# dc10_revA.net
KiCad netlist of a schematic drawn in EAGLE
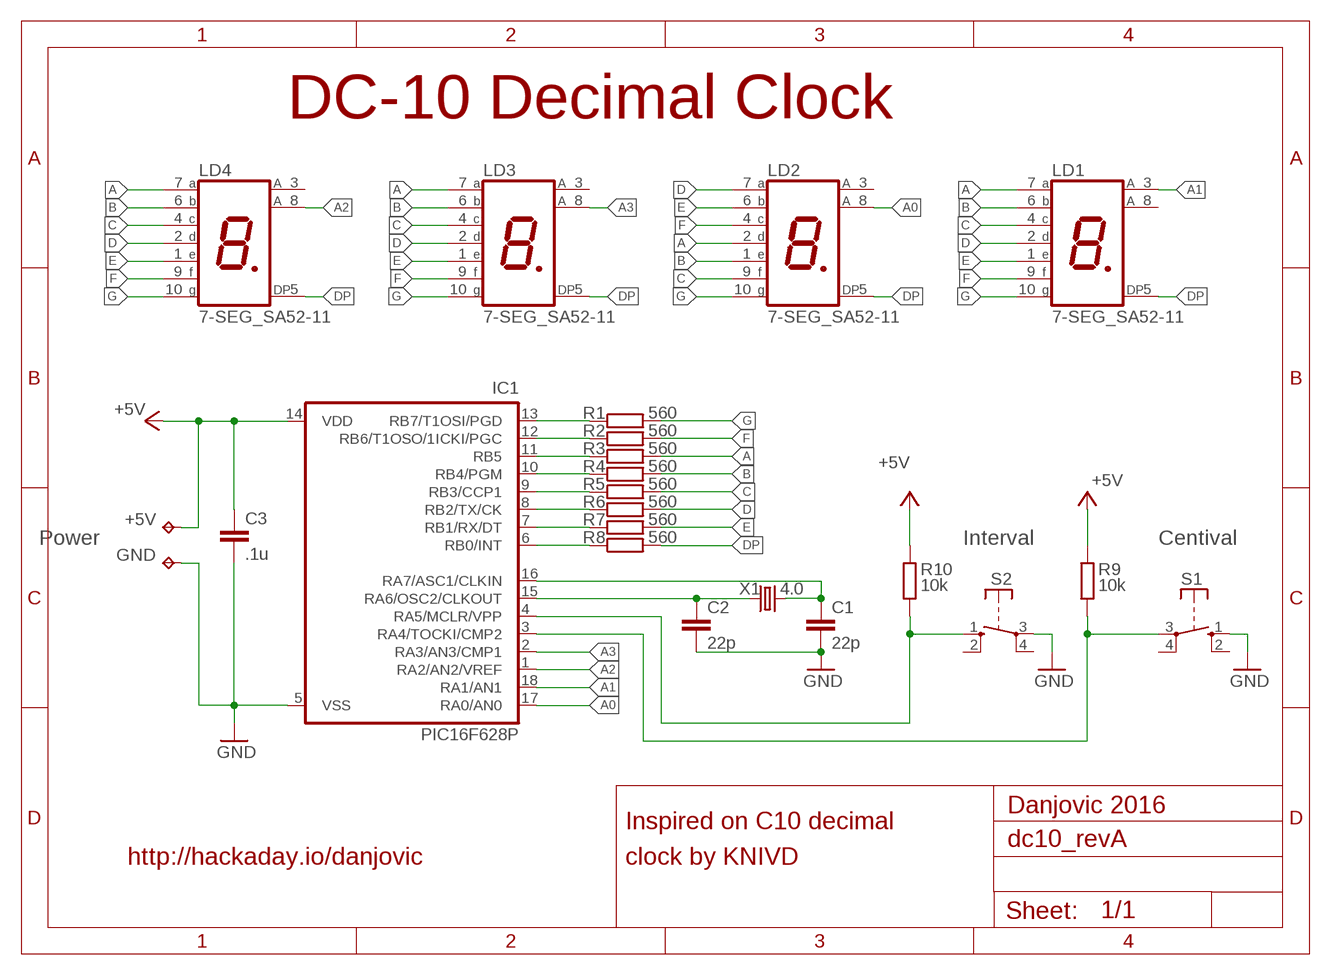
[diagram p0: schematic, sheet 1]

(export (version "E")
  (design (tool "Eeschema 10.0.6"))
  (components
    (comp (ref "+5V")
      (value "TPPAD1-13")
      (footprint "eagle-import:P1-13")
      (libsource (lib "eagle-import") (part "TPPAD1-13"))
    )
    (comp (ref "C1")
      (value "22p")
      (footprint "eagle-import:C050-024X044")
      (libsource (lib "eagle-import") (part "C-EU050-024X044"))
    )
    (comp (ref "C2")
      (value "22p")
      (footprint "eagle-import:C050-024X044")
      (libsource (lib "eagle-import") (part "C-EU050-024X044"))
    )
    (comp (ref "C3")
      (value ".1u")
      (footprint "eagle-import:C050-024X044")
      (libsource (lib "eagle-import") (part "C-EU050-024X044"))
    )
    (comp (ref "GND")
      (value "TPPAD1-13")
      (footprint "eagle-import:P1-13")
      (libsource (lib "eagle-import") (part "TPPAD1-13"))
    )
    (comp (ref "IC1")
      (value "PIC16F628P")
      (footprint "eagle-import:DIL18")
      (libsource (lib "eagle-import") (part "PIC16F628P"))
    )
    (comp (ref "LD1")
      (value "7-SEG_SA52-11")
      (footprint "eagle-import:SA52-11")
      (libsource (lib "eagle-import") (part "7-SEG_SA52-11"))
    )
    (comp (ref "LD2")
      (value "7-SEG_SA52-11")
      (footprint "eagle-import:SA52-11")
      (libsource (lib "eagle-import") (part "7-SEG_SA52-11"))
    )
    (comp (ref "LD3")
      (value "7-SEG_SA52-11")
      (footprint "eagle-import:SA52-11")
      (libsource (lib "eagle-import") (part "7-SEG_SA52-11"))
    )
    (comp (ref "LD4")
      (value "7-SEG_SA52-11")
      (footprint "eagle-import:SA52-11")
      (libsource (lib "eagle-import") (part "7-SEG_SA52-11"))
    )
    (comp (ref "R1")
      (value "560")
      (footprint "eagle-import:0204_7")
      (libsource (lib "eagle-import") (part "R-EU_0204/7"))
    )
    (comp (ref "R2")
      (value "560")
      (footprint "eagle-import:0204_7")
      (libsource (lib "eagle-import") (part "R-EU_0204/7"))
    )
    (comp (ref "R3")
      (value "560")
      (footprint "eagle-import:0204_7")
      (libsource (lib "eagle-import") (part "R-EU_0204/7"))
    )
    (comp (ref "R4")
      (value "560")
      (footprint "eagle-import:0204_7")
      (libsource (lib "eagle-import") (part "R-EU_0204/7"))
    )
    (comp (ref "R5")
      (value "560")
      (footprint "eagle-import:0204_7")
      (libsource (lib "eagle-import") (part "R-EU_0204/7"))
    )
    (comp (ref "R6")
      (value "560")
      (footprint "eagle-import:0204_7")
      (libsource (lib "eagle-import") (part "R-EU_0204/7"))
    )
    (comp (ref "R7")
      (value "560")
      (footprint "eagle-import:0204_7")
      (libsource (lib "eagle-import") (part "R-EU_0204/7"))
    )
    (comp (ref "R8")
      (value "560")
      (footprint "eagle-import:0204_7")
      (libsource (lib "eagle-import") (part "R-EU_0204/7"))
    )
    (comp (ref "R9")
      (value "10k")
      (footprint "eagle-import:0204_7")
      (libsource (lib "eagle-import") (part "R-EU_0204/7"))
    )
    (comp (ref "R10")
      (value "10k")
      (footprint "eagle-import:0204_7")
      (libsource (lib "eagle-import") (part "R-EU_0204/7"))
    )
    (comp (ref "S1")
      (value "RACON12")
      (footprint "eagle-import:RACON12")
      (libsource (lib "eagle-import") (part "RACON12"))
    )
    (comp (ref "S2")
      (value "RACON12")
      (footprint "eagle-import:RACON12")
      (libsource (lib "eagle-import") (part "RACON12"))
    )
    (comp (ref "X1")
      (value "4.0")
      (footprint "eagle-import:HC49U-V")
      (libsource (lib "eagle-import") (part "CRYSTALHC49U-V"))
    )
  )
  (nets
    (net (code "1") (name "+5V") (class "Default")
      (node (ref "+5V") (pin "1") (pinfunction "TP_1") (pintype "input"))
      (node (ref "C3") (pin "1") (pinfunction "1_1") (pintype "passive"))
      (node (ref "IC1") (pin "14") (pinfunction "VDD_14") (pintype "power_in"))
      (node (ref "R10") (pin "1") (pinfunction "1_1") (pintype "passive"))
      (node (ref "R9") (pin "1") (pinfunction "1_1") (pintype "passive"))
    )
    (net (code "2") (name "A") (class "Default")
      (node (ref "LD1") (pin "7") (pinfunction "A_7") (pintype "passive"))
      (node (ref "LD2") (pin "2") (pinfunction "D_2") (pintype "passive"))
      (node (ref "LD3") (pin "7") (pinfunction "A_7") (pintype "passive"))
      (node (ref "LD4") (pin "7") (pinfunction "A_7") (pintype "passive"))
      (node (ref "R3") (pin "2") (pinfunction "2_2") (pintype "passive"))
    )
    (net (code "3") (name "A0") (class "Default")
      (node (ref "IC1") (pin "17") (pinfunction "RA0/AN0_17") (pintype "bidirectional"))
      (node (ref "LD2") (pin "8") (pinfunction "A_8") (pintype "passive"))
    )
    (net (code "4") (name "A1") (class "Default")
      (node (ref "IC1") (pin "18") (pinfunction "RA1/AN1_18") (pintype "bidirectional"))
      (node (ref "LD1") (pin "3") (pinfunction "A_3") (pintype "passive"))
    )
    (net (code "5") (name "A2") (class "Default")
      (node (ref "IC1") (pin "1") (pinfunction "RA2/AN2/VREF_1") (pintype "bidirectional"))
      (node (ref "LD4") (pin "8") (pinfunction "A_8") (pintype "passive"))
    )
    (net (code "6") (name "A3") (class "Default")
      (node (ref "IC1") (pin "2") (pinfunction "RA3/AN3/CMP1_2") (pintype "bidirectional"))
      (node (ref "LD3") (pin "8") (pinfunction "A_8") (pintype "passive"))
    )
    (net (code "7") (name "B") (class "Default")
      (node (ref "LD1") (pin "6") (pinfunction "B_6") (pintype "passive"))
      (node (ref "LD2") (pin "1") (pinfunction "E_1") (pintype "passive"))
      (node (ref "LD3") (pin "6") (pinfunction "B_6") (pintype "passive"))
      (node (ref "LD4") (pin "6") (pinfunction "B_6") (pintype "passive"))
      (node (ref "R4") (pin "2") (pinfunction "2_2") (pintype "passive"))
    )
    (net (code "8") (name "C") (class "Default")
      (node (ref "LD1") (pin "4") (pinfunction "C_4") (pintype "passive"))
      (node (ref "LD2") (pin "9") (pinfunction "F_9") (pintype "passive"))
      (node (ref "LD3") (pin "4") (pinfunction "C_4") (pintype "passive"))
      (node (ref "LD4") (pin "4") (pinfunction "C_4") (pintype "passive"))
      (node (ref "R5") (pin "2") (pinfunction "2_2") (pintype "passive"))
    )
    (net (code "9") (name "D") (class "Default")
      (node (ref "LD1") (pin "2") (pinfunction "D_2") (pintype "passive"))
      (node (ref "LD2") (pin "7") (pinfunction "A_7") (pintype "passive"))
      (node (ref "LD3") (pin "2") (pinfunction "D_2") (pintype "passive"))
      (node (ref "LD4") (pin "2") (pinfunction "D_2") (pintype "passive"))
      (node (ref "R6") (pin "2") (pinfunction "2_2") (pintype "passive"))
    )
    (net (code "10") (name "DP") (class "Default")
      (node (ref "LD1") (pin "5") (pinfunction "DP_5") (pintype "passive"))
      (node (ref "LD2") (pin "5") (pinfunction "DP_5") (pintype "passive"))
      (node (ref "LD3") (pin "5") (pinfunction "DP_5") (pintype "passive"))
      (node (ref "LD4") (pin "5") (pinfunction "DP_5") (pintype "passive"))
      (node (ref "R8") (pin "2") (pinfunction "2_2") (pintype "passive"))
    )
    (net (code "11") (name "E") (class "Default")
      (node (ref "LD1") (pin "1") (pinfunction "E_1") (pintype "passive"))
      (node (ref "LD2") (pin "6") (pinfunction "B_6") (pintype "passive"))
      (node (ref "LD3") (pin "1") (pinfunction "E_1") (pintype "passive"))
      (node (ref "LD4") (pin "1") (pinfunction "E_1") (pintype "passive"))
      (node (ref "R7") (pin "2") (pinfunction "2_2") (pintype "passive"))
    )
    (net (code "12") (name "F") (class "Default")
      (node (ref "LD1") (pin "9") (pinfunction "F_9") (pintype "passive"))
      (node (ref "LD2") (pin "4") (pinfunction "C_4") (pintype "passive"))
      (node (ref "LD3") (pin "9") (pinfunction "F_9") (pintype "passive"))
      (node (ref "LD4") (pin "9") (pinfunction "F_9") (pintype "passive"))
      (node (ref "R2") (pin "2") (pinfunction "2_2") (pintype "passive"))
    )
    (net (code "13") (name "G") (class "Default")
      (node (ref "LD1") (pin "10") (pinfunction "G_10") (pintype "passive"))
      (node (ref "LD2") (pin "10") (pinfunction "G_10") (pintype "passive"))
      (node (ref "LD3") (pin "10") (pinfunction "G_10") (pintype "passive"))
      (node (ref "LD4") (pin "10") (pinfunction "G_10") (pintype "passive"))
      (node (ref "R1") (pin "2") (pinfunction "2_2") (pintype "passive"))
    )
    (net (code "14") (name "GND") (class "Default")
      (node (ref "C1") (pin "2") (pinfunction "2_2") (pintype "passive"))
      (node (ref "C2") (pin "2") (pinfunction "2_2") (pintype "passive"))
      (node (ref "C3") (pin "2") (pinfunction "2_2") (pintype "passive"))
      (node (ref "GND") (pin "1") (pinfunction "TP_1") (pintype "input"))
      (node (ref "IC1") (pin "5") (pinfunction "VSS_5") (pintype "power_in"))
      (node (ref "S1") (pin "1") (pinfunction "S_1") (pintype "passive"))
      (node (ref "S2") (pin "3") (pinfunction "P_3") (pintype "passive"))
    )
    (net (code "15") (name "Net-(IC1-RA4{slash}TOCKI{slash}CMP2)") (class "Default")
      (node (ref "IC1") (pin "3") (pinfunction "RA4/TOCKI/CMP2_3") (pintype "bidirectional"))
      (node (ref "R9") (pin "2") (pinfunction "2_2") (pintype "passive"))
      (node (ref "S1") (pin "3") (pinfunction "P_3") (pintype "passive"))
    )
    (net (code "16") (name "Net-(IC1-RA5{slash}MCLR{slash}VPP)") (class "Default")
      (node (ref "IC1") (pin "4") (pinfunction "RA5/MCLR/VPP_4") (pintype "input"))
      (node (ref "R10") (pin "2") (pinfunction "2_2") (pintype "passive"))
      (node (ref "S2") (pin "1") (pinfunction "S_1") (pintype "passive"))
    )
    (net (code "17") (name "Net-(IC1-RA6{slash}OSC2{slash}CLKOUT)") (class "Default")
      (node (ref "C2") (pin "1") (pinfunction "1_1") (pintype "passive"))
      (node (ref "IC1") (pin "15") (pinfunction "RA6/OSC2/CLKOUT_15") (pintype "bidirectional"))
      (node (ref "X1") (pin "1") (pinfunction "1_1") (pintype "passive"))
    )
    (net (code "18") (name "Net-(IC1-RA7{slash}ASC1{slash}CLKIN)") (class "Default")
      (node (ref "C1") (pin "1") (pinfunction "1_1") (pintype "passive"))
      (node (ref "IC1") (pin "16") (pinfunction "RA7/ASC1/CLKIN_16") (pintype "bidirectional"))
      (node (ref "X1") (pin "2") (pinfunction "2_2") (pintype "passive"))
    )
    (net (code "19") (name "Net-(IC1-RB0{slash}INT)") (class "Default")
      (node (ref "IC1") (pin "6") (pinfunction "RB0/INT_6") (pintype "bidirectional"))
      (node (ref "R8") (pin "1") (pinfunction "1_1") (pintype "passive"))
    )
    (net (code "20") (name "Net-(IC1-RB1{slash}RX{slash}DT)") (class "Default")
      (node (ref "IC1") (pin "7") (pinfunction "RB1/RX/DT_7") (pintype "bidirectional"))
      (node (ref "R7") (pin "1") (pinfunction "1_1") (pintype "passive"))
    )
    (net (code "21") (name "Net-(IC1-RB2{slash}TX{slash}CK)") (class "Default")
      (node (ref "IC1") (pin "8") (pinfunction "RB2/TX/CK_8") (pintype "bidirectional"))
      (node (ref "R6") (pin "1") (pinfunction "1_1") (pintype "passive"))
    )
    (net (code "22") (name "Net-(IC1-RB3{slash}CCP1)") (class "Default")
      (node (ref "IC1") (pin "9") (pinfunction "RB3/CCP1_9") (pintype "bidirectional"))
      (node (ref "R5") (pin "1") (pinfunction "1_1") (pintype "passive"))
    )
    (net (code "23") (name "Net-(IC1-RB4{slash}PGM)") (class "Default")
      (node (ref "IC1") (pin "10") (pinfunction "RB4/PGM_10") (pintype "bidirectional"))
      (node (ref "R4") (pin "1") (pinfunction "1_1") (pintype "passive"))
    )
    (net (code "24") (name "Net-(IC1-RB5)") (class "Default")
      (node (ref "IC1") (pin "11") (pinfunction "RB5_11") (pintype "bidirectional"))
      (node (ref "R3") (pin "1") (pinfunction "1_1") (pintype "passive"))
    )
    (net (code "25") (name "Net-(IC1-RB6{slash}T1OSO{slash}1ICKI{slash}PGC)") (class "Default")
      (node (ref "IC1") (pin "12") (pinfunction "RB6/T1OSO/1ICKI/PGC_12") (pintype "bidirectional"))
      (node (ref "R2") (pin "1") (pinfunction "1_1") (pintype "passive"))
    )
    (net (code "26") (name "Net-(IC1-RB7{slash}T1OSI{slash}PGD)") (class "Default")
      (node (ref "IC1") (pin "13") (pinfunction "RB7/T1OSI/PGD_13") (pintype "bidirectional"))
      (node (ref "R1") (pin "1") (pinfunction "1_1") (pintype "passive"))
    )
    (net (code "27") (name "unconnected-(LD1-A-Pad8)") (class "Default")
      (node (ref "LD1") (pin "8") (pinfunction "A_8") (pintype "passive"))
    )
    (net (code "28") (name "unconnected-(LD2-A-Pad3)") (class "Default")
      (node (ref "LD2") (pin "3") (pinfunction "A_3") (pintype "passive"))
    )
    (net (code "29") (name "unconnected-(LD3-A-Pad3)") (class "Default")
      (node (ref "LD3") (pin "3") (pinfunction "A_3") (pintype "passive"))
    )
    (net (code "30") (name "unconnected-(LD4-A-Pad3)") (class "Default")
      (node (ref "LD4") (pin "3") (pinfunction "A_3") (pintype "passive"))
    )
    (net (code "31") (name "unconnected-(S1-P-Pad4)") (class "Default")
      (node (ref "S1") (pin "4") (pinfunction "P_4") (pintype "passive"))
    )
    (net (code "32") (name "unconnected-(S1-S-Pad2)") (class "Default")
      (node (ref "S1") (pin "2") (pinfunction "S_2") (pintype "passive"))
    )
    (net (code "33") (name "unconnected-(S2-P-Pad4)") (class "Default")
      (node (ref "S2") (pin "4") (pinfunction "P_4") (pintype "passive"))
    )
    (net (code "34") (name "unconnected-(S2-S-Pad2)") (class "Default")
      (node (ref "S2") (pin "2") (pinfunction "S_2") (pintype "passive"))
    )
  )
)
